# DC075B_POWER_SUPPLIES.net
KiCad netlist of a schematic drawn in Altium Designer
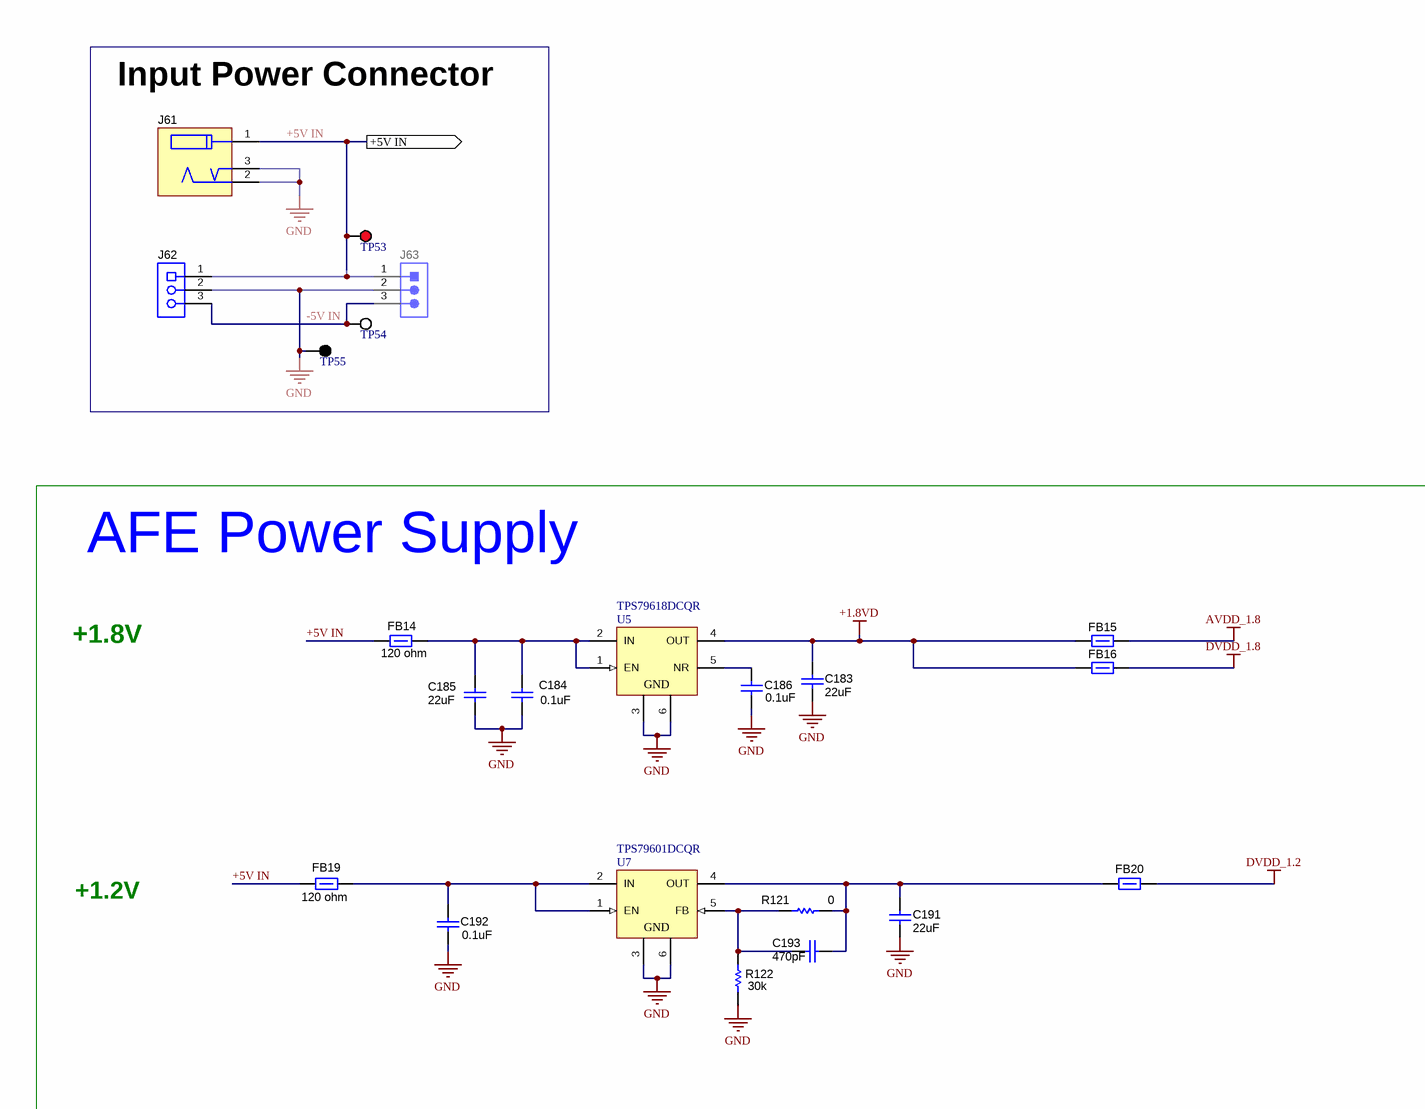
[diagram p0: DC075B_POWER_SUPPLIES.SchDoc, top left]
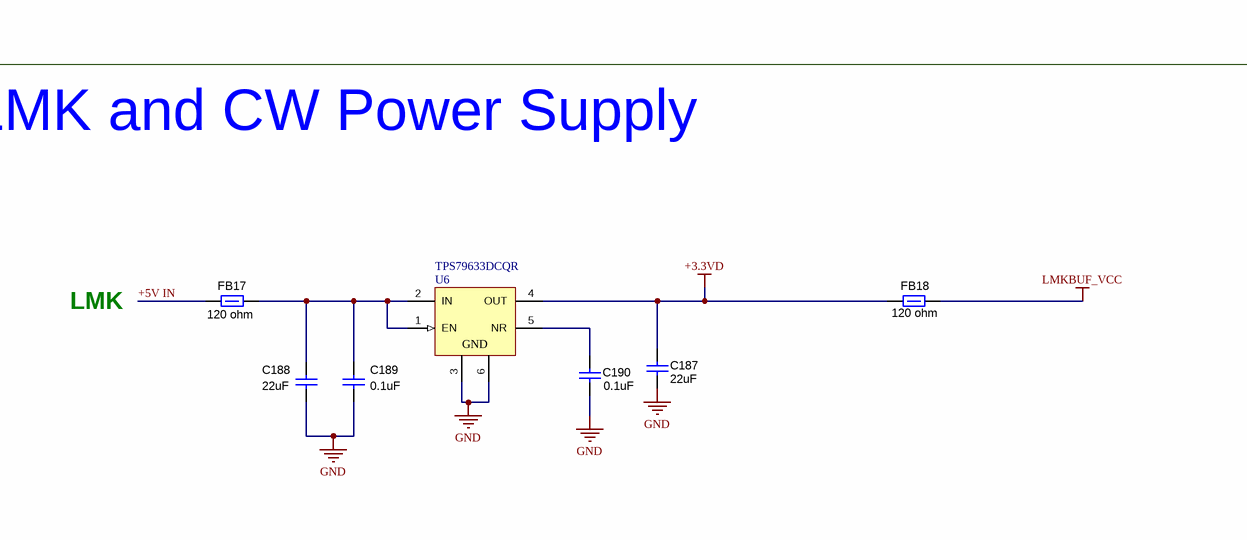
[diagram p1: DC075B_POWER_SUPPLIES.SchDoc, top right]
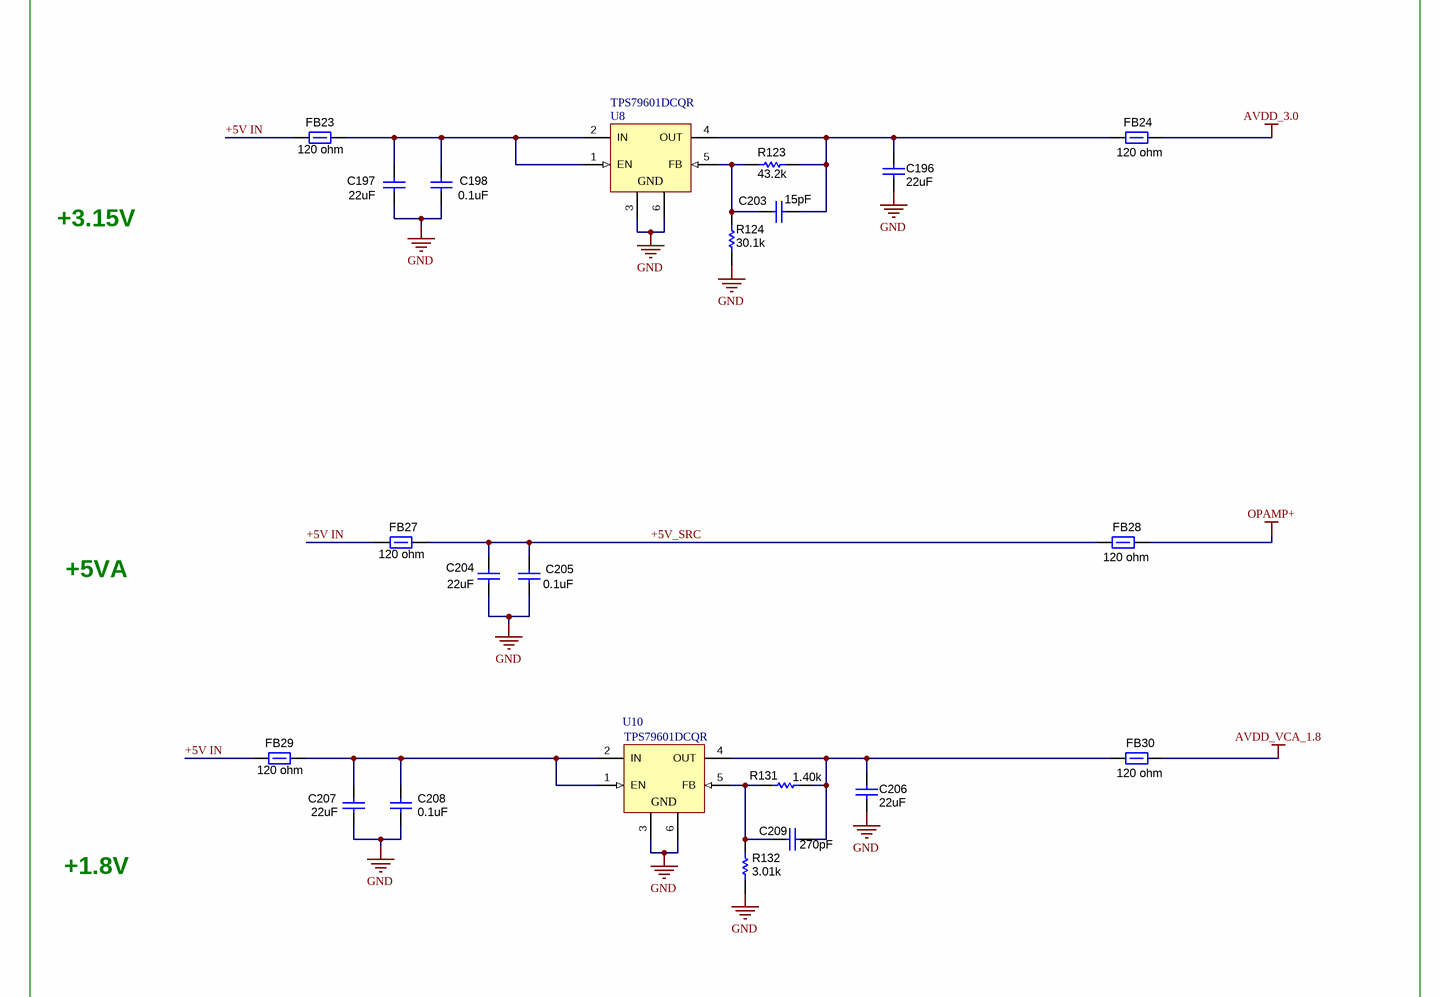
[diagram p2: DC075B_POWER_SUPPLIES.SchDoc, bottom left]
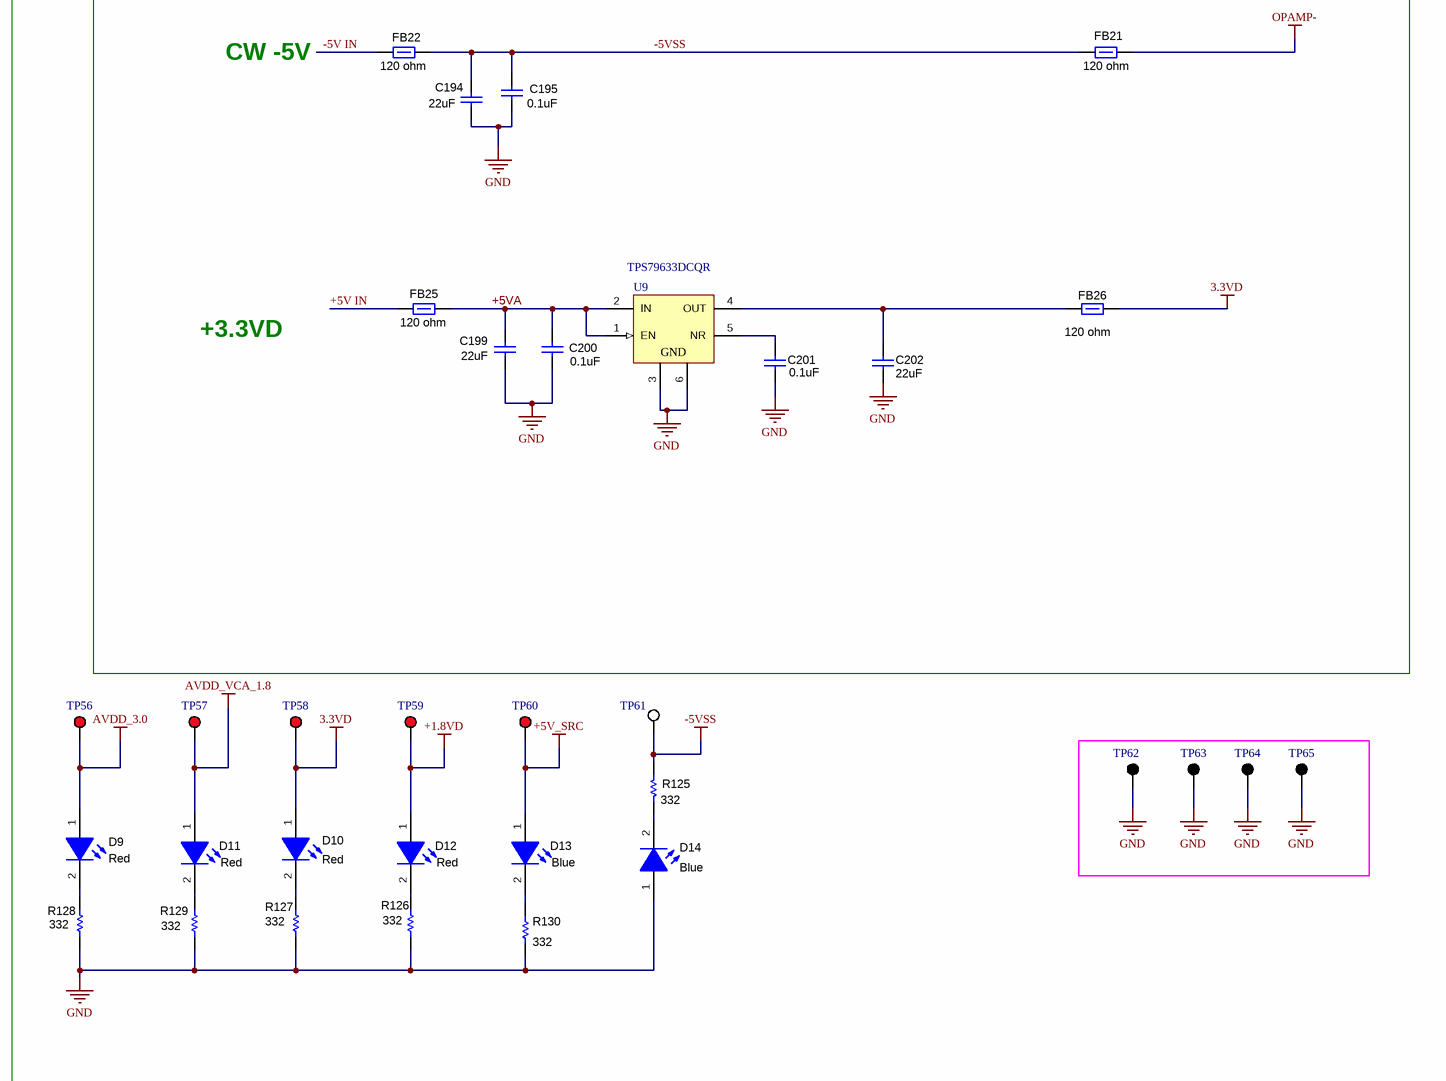
[diagram p3: DC075B_POWER_SUPPLIES.SchDoc, bottom right]

(export (version "E")
  (design (tool "Eeschema 10.0.6"))
  (components
    (comp (ref "C183")
      (value "GRM187R61A226ME15D")
      (footprint "0603")
      (description "CAP, CERM, 22 uF, 10 V, +/- 20%, X5R, 0603")
      (fields
        (field (name "VALUEDISPLAYED") "22uF")
        (field (name "MANUFACTURER") "MuRata")
        (field (name "PUBLISHER") "Texas Instruments")
      )
      (libsource (lib "Altium Vault - TI") (part "Capacitor"))
    )
    (comp (ref "C184")
      (value "0.1uF")
      (footprint "0603")
      (description "CAP, CERM, 0.1 µF, 25 V,+/- 10%, X5R, 0603")
      (fields
        (field (name "PARTNUMBER") "CL10A104KA8NNNC")
        (field (name "MANUFACTURER") "Samsung Electro-Mechanics")
      )
      (libsource (lib "Altium Vault - TI") (part "Capacitor"))
    )
    (comp (ref "C185")
      (value "1206YD226MAT2A")
      (footprint "1206_190")
      (description "CAP, CERM, 22 uF, 16 V, +/- 20%, X5R, 1206_190")
      (fields
        (field (name "VALUEDISPLAYED") "22uF")
        (field (name "MANUFACTURER") "AVX")
        (field (name "PUBLISHER") "Texas Instruments")
      )
      (libsource (lib "Altium Vault - TI") (part "Capacitor"))
    )
    (comp (ref "C186")
      (value "0.1uF")
      (footprint "0603")
      (description "CAP, CERM, 0.1 µF, 25 V,+/- 10%, X5R, 0603")
      (fields
        (field (name "PARTNUMBER") "CL10A104KA8NNNC")
        (field (name "MANUFACTURER") "Samsung Electro-Mechanics")
      )
      (libsource (lib "Altium Vault - TI") (part "Capacitor"))
    )
    (comp (ref "C187")
      (value "GRM187R61A226ME15D")
      (footprint "0603")
      (description "CAP, CERM, 22 uF, 10 V, +/- 20%, X5R, 0603")
      (fields
        (field (name "VALUEDISPLAYED") "22uF")
        (field (name "MANUFACTURER") "MuRata")
        (field (name "PUBLISHER") "Texas Instruments")
      )
      (libsource (lib "Altium Vault - TI") (part "Capacitor"))
    )
    (comp (ref "C188")
      (value "1206YD226MAT2A")
      (footprint "1206_190")
      (description "CAP, CERM, 22 uF, 16 V, +/- 20%, X5R, 1206_190")
      (fields
        (field (name "VALUEDISPLAYED") "22uF")
        (field (name "MANUFACTURER") "AVX")
        (field (name "PUBLISHER") "Texas Instruments")
      )
      (libsource (lib "Altium Vault - TI") (part "Capacitor"))
    )
    (comp (ref "C189")
      (value "0.1uF")
      (footprint "0603")
      (description "CAP, CERM, 0.1 µF, 25 V,+/- 10%, X5R, 0603")
      (fields
        (field (name "PARTNUMBER") "CL10A104KA8NNNC")
        (field (name "MANUFACTURER") "Samsung Electro-Mechanics")
      )
      (libsource (lib "Altium Vault - TI") (part "Capacitor"))
    )
    (comp (ref "C190")
      (value "0.1uF")
      (footprint "0603")
      (description "CAP, CERM, 0.1 µF, 25 V,+/- 10%, X5R, 0603")
      (fields
        (field (name "PARTNUMBER") "CL10A104KA8NNNC")
        (field (name "MANUFACTURER") "Samsung Electro-Mechanics")
      )
      (libsource (lib "Altium Vault - TI") (part "Capacitor"))
    )
    (comp (ref "C191")
      (value "GRM187R61A226ME15D")
      (footprint "0603")
      (description "CAP, CERM, 22 uF, 10 V, +/- 20%, X5R, 0603")
      (fields
        (field (name "VALUEDISPLAYED") "22uF")
        (field (name "MANUFACTURER") "MuRata")
        (field (name "PUBLISHER") "Texas Instruments")
      )
      (libsource (lib "Altium Vault - TI") (part "Capacitor"))
    )
    (comp (ref "C192")
      (value "0.1uF")
      (footprint "0603")
      (description "CAP, CERM, 0.1 µF, 25 V,+/- 10%, X5R, 0603")
      (fields
        (field (name "PARTNUMBER") "CL10A104KA8NNNC")
        (field (name "MANUFACTURER") "Samsung Electro-Mechanics")
      )
      (libsource (lib "Altium Vault - TI") (part "Capacitor"))
    )
    (comp (ref "C193")
      (value "470pF")
      (footprint "0603")
      (description "CAP, CERM, 470 pF, 50 V, +/- 5%, C0G/NP0, 0603")
      (fields
        (field (name "PARTNUMBER") "06035A471JAT2A")
        (field (name "MANUFACTURER") "AVX")
        (field (name "PUBLISHER") "Texas Instruments")
      )
      (libsource (lib "Altium Vault - TI") (part "Capacitor"))
    )
    (comp (ref "C194")
      (value "1206YD226MAT2A")
      (footprint "1206_190")
      (description "CAP, CERM, 22 uF, 16 V, +/- 20%, X5R, 1206_190")
      (fields
        (field (name "VALUEDISPLAYED") "22uF")
        (field (name "MANUFACTURER") "AVX")
        (field (name "PUBLISHER") "Texas Instruments")
      )
      (libsource (lib "Altium Vault - TI") (part "Capacitor"))
    )
    (comp (ref "C195")
      (value "0.1uF")
      (footprint "0603")
      (description "CAP, CERM, 0.1 µF, 25 V,+/- 10%, X5R, 0603")
      (fields
        (field (name "PARTNUMBER") "CL10A104KA8NNNC")
        (field (name "MANUFACTURER") "Samsung Electro-Mechanics")
      )
      (libsource (lib "Altium Vault - TI") (part "Capacitor"))
    )
    (comp (ref "C196")
      (value "GRM187R61A226ME15D")
      (footprint "0603")
      (description "CAP, CERM, 22 uF, 10 V, +/- 20%, X5R, 0603")
      (fields
        (field (name "VALUEDISPLAYED") "22uF")
        (field (name "MANUFACTURER") "MuRata")
        (field (name "PUBLISHER") "Texas Instruments")
      )
      (libsource (lib "Altium Vault - TI") (part "Capacitor"))
    )
    (comp (ref "C197")
      (value "1206YD226MAT2A")
      (footprint "1206_190")
      (description "CAP, CERM, 22 uF, 16 V, +/- 20%, X5R, 1206_190")
      (fields
        (field (name "VALUEDISPLAYED") "22uF")
        (field (name "MANUFACTURER") "AVX")
        (field (name "PUBLISHER") "Texas Instruments")
      )
      (libsource (lib "Altium Vault - TI") (part "Capacitor"))
    )
    (comp (ref "C198")
      (value "0.1uF")
      (footprint "0603")
      (description "CAP, CERM, 0.1 µF, 25 V,+/- 10%, X5R, 0603")
      (fields
        (field (name "PARTNUMBER") "CL10A104KA8NNNC")
        (field (name "MANUFACTURER") "Samsung Electro-Mechanics")
      )
      (libsource (lib "Altium Vault - TI") (part "Capacitor"))
    )
    (comp (ref "C199")
      (value "1206YD226MAT2A")
      (footprint "1206_190")
      (description "CAP, CERM, 22 uF, 16 V, +/- 20%, X5R, 1206_190")
      (fields
        (field (name "VALUEDISPLAYED") "22uF")
        (field (name "MANUFACTURER") "AVX")
        (field (name "PUBLISHER") "Texas Instruments")
      )
      (libsource (lib "Altium Vault - TI") (part "Capacitor"))
    )
    (comp (ref "C200")
      (value "0.1uF")
      (footprint "0603")
      (description "CAP, CERM, 0.1 µF, 25 V,+/- 10%, X5R, 0603")
      (fields
        (field (name "PARTNUMBER") "CL10A104KA8NNNC")
        (field (name "MANUFACTURER") "Samsung Electro-Mechanics")
      )
      (libsource (lib "Altium Vault - TI") (part "Capacitor"))
    )
    (comp (ref "C201")
      (value "0.1uF")
      (footprint "0603")
      (description "CAP, CERM, 0.1 µF, 25 V,+/- 10%, X5R, 0603")
      (fields
        (field (name "PARTNUMBER") "CL10A104KA8NNNC")
        (field (name "MANUFACTURER") "Samsung Electro-Mechanics")
      )
      (libsource (lib "Altium Vault - TI") (part "Capacitor"))
    )
    (comp (ref "C202")
      (value "GRM187R61A226ME15D")
      (footprint "0603")
      (description "CAP, CERM, 22 uF, 10 V, +/- 20%, X5R, 0603")
      (fields
        (field (name "VALUEDISPLAYED") "22uF")
        (field (name "MANUFACTURER") "MuRata")
        (field (name "PUBLISHER") "Texas Instruments")
      )
      (libsource (lib "Altium Vault - TI") (part "Capacitor"))
    )
    (comp (ref "C203")
      (value "06035A150JAT2A")
      (footprint "0603")
      (description "CAP, CERM, 15 pF, 50 V, +/- 5%, C0G/NP0, 0603")
      (fields
        (field (name "VALUEDISPLAYED") "15pF")
        (field (name "MANUFACTURER") "AVX")
        (field (name "PUBLISHER") "Texas Instruments")
      )
      (libsource (lib "Altium Vault - TI") (part "Capacitor"))
    )
    (comp (ref "C204")
      (value "1206YD226MAT2A")
      (footprint "1206_190")
      (description "CAP, CERM, 22 uF, 16 V, +/- 20%, X5R, 1206_190")
      (fields
        (field (name "VALUEDISPLAYED") "22uF")
        (field (name "MANUFACTURER") "AVX")
        (field (name "PUBLISHER") "Texas Instruments")
      )
      (libsource (lib "Altium Vault - TI") (part "Capacitor"))
    )
    (comp (ref "C205")
      (value "0.1uF")
      (footprint "0603")
      (description "CAP, CERM, 0.1 µF, 25 V,+/- 10%, X5R, 0603")
      (fields
        (field (name "PARTNUMBER") "CL10A104KA8NNNC")
        (field (name "MANUFACTURER") "Samsung Electro-Mechanics")
      )
      (libsource (lib "Altium Vault - TI") (part "Capacitor"))
    )
    (comp (ref "C206")
      (value "GRM187R61A226ME15D")
      (footprint "0603")
      (description "CAP, CERM, 22 uF, 10 V, +/- 20%, X5R, 0603")
      (fields
        (field (name "VALUEDISPLAYED") "22uF")
        (field (name "MANUFACTURER") "MuRata")
        (field (name "PUBLISHER") "Texas Instruments")
      )
      (libsource (lib "Altium Vault - TI") (part "Capacitor"))
    )
    (comp (ref "C207")
      (value "1206YD226MAT2A")
      (footprint "1206_190")
      (description "CAP, CERM, 22 uF, 16 V, +/- 20%, X5R, 1206_190")
      (fields
        (field (name "VALUEDISPLAYED") "22uF")
        (field (name "MANUFACTURER") "AVX")
        (field (name "PUBLISHER") "Texas Instruments")
      )
      (libsource (lib "Altium Vault - TI") (part "Capacitor"))
    )
    (comp (ref "C208")
      (value "0.1uF")
      (footprint "0603")
      (description "CAP, CERM, 0.1 µF, 25 V,+/- 10%, X5R, 0603")
      (fields
        (field (name "PARTNUMBER") "CL10A104KA8NNNC")
        (field (name "MANUFACTURER") "Samsung Electro-Mechanics")
      )
      (libsource (lib "Altium Vault - TI") (part "Capacitor"))
    )
    (comp (ref "C209")
      (value "C0603C271K5RACTU")
      (footprint "0603")
      (description "CAP, CERM, 270 pF, 50 V, +/- 10%, X7R, 0603")
      (fields
        (field (name "MANUFACTURER") "Kemet")
        (field (name "CAP_F") "270pF")
        (field (name "PUBLISHER") "Texas Instruments")
      )
      (libsource (lib "Altium Vault - TI") (part "Capacitor"))
    )
    (comp (ref "D9")
      (value "Red")
      (footprint "LED_LTST-C190_Red")
      (description "LED, Red, SMD")
      (fields (field (name "MANUFACTURER") "Lite-On") (field (name "PARTNUMBER") "LTST-C190CKT"))
      (libsource (lib "Altium Vault - TI") (part "CMP-0002842-2"))
    )
    (comp (ref "D10")
      (value "Red")
      (footprint "LED_LTST-C190_Red")
      (description "LED, Red, SMD")
      (fields (field (name "MANUFACTURER") "Lite-On") (field (name "PARTNUMBER") "LTST-C190CKT"))
      (libsource (lib "Altium Vault - TI") (part "CMP-0002842-2"))
    )
    (comp (ref "D11")
      (value "Red")
      (footprint "LED_LTST-C190_Red")
      (description "LED, Red, SMD")
      (fields (field (name "MANUFACTURER") "Lite-On") (field (name "PARTNUMBER") "LTST-C190CKT"))
      (libsource (lib "Altium Vault - TI") (part "CMP-0002842-2"))
    )
    (comp (ref "D12")
      (value "Red")
      (footprint "LED_LTST-C190_Red")
      (description "LED, Red, SMD")
      (fields (field (name "MANUFACTURER") "Lite-On") (field (name "PARTNUMBER") "LTST-C190CKT"))
      (libsource (lib "Altium Vault - TI") (part "CMP-0002842-2"))
    )
    (comp (ref "D13")
      (value "Blue")
      (footprint "LB Q39G_BLUE")
      (description "LED, Blue, SMD")
      (fields (field (name "MANUFACTURER") "OSRAM") (field (name "PARTNUMBER") "LB Q39G-L2N2-35-1"))
      (libsource (lib "Altium Vault - TI") (part "CMP-0002849-2"))
    )
    (comp (ref "D14")
      (value "Blue")
      (footprint "LB Q39G_BLUE")
      (description "LED, Blue, SMD")
      (fields (field (name "MANUFACTURER") "OSRAM") (field (name "PARTNUMBER") "LB Q39G-L2N2-35-1"))
      (libsource (lib "Altium Vault - TI") (part "CMP-0002849-2"))
    )
    (comp (ref "FB14")
      (value "120 ohm")
      (footprint "0805")
      (description "Ferrite Bead, 120 ohm @ 100 MHz, 0.8 A, 0805")
      (fields
        (field (name "MANUFACTURER") "MuRata")
        (field (name "PARTNUMBER") "BLM21AG121SN1D")
        (field (name "PUBLISHER") "Texas Instruments")
      )
      (libsource (lib "Altium Vault - TI") (part "Ferrite_Bead"))
    )
    (comp (ref "FB15")
      (value "BLM21AG121SN1D")
      (footprint "0805")
      (description "Ferrite Bead, 120 ohm @ 100 MHz, 0.8 A, 0805")
      (fields (field (name "MANUFACTURER") "MuRata") (field (name "PUBLISHER") "Texas Instruments"))
      (libsource (lib "Altium Vault - TI") (part "Ferrite_Bead"))
    )
    (comp (ref "FB16")
      (value "BLM21AG121SN1D")
      (footprint "0805")
      (description "Ferrite Bead, 120 ohm @ 100 MHz, 0.8 A, 0805")
      (fields (field (name "MANUFACTURER") "MuRata") (field (name "PUBLISHER") "Texas Instruments"))
      (libsource (lib "Altium Vault - TI") (part "Ferrite_Bead"))
    )
    (comp (ref "FB17")
      (value "120 ohm")
      (footprint "0805")
      (description "Ferrite Bead, 120 ohm @ 100 MHz, 0.8 A, 0805")
      (fields
        (field (name "MANUFACTURER") "MuRata")
        (field (name "PARTNUMBER") "BLM21AG121SN1D")
        (field (name "PUBLISHER") "Texas Instruments")
      )
      (libsource (lib "Altium Vault - TI") (part "Ferrite_Bead"))
    )
    (comp (ref "FB18")
      (value "120 ohm")
      (footprint "0805")
      (description "Ferrite Bead, 120 ohm @ 100 MHz, 0.8 A, 0805")
      (fields
        (field (name "MANUFACTURER") "MuRata")
        (field (name "PARTNUMBER") "BLM21AG121SN1D")
        (field (name "PUBLISHER") "Texas Instruments")
      )
      (libsource (lib "Altium Vault - TI") (part "Ferrite_Bead"))
    )
    (comp (ref "FB19")
      (value "120 ohm")
      (footprint "0805")
      (description "Ferrite Bead, 120 ohm @ 100 MHz, 0.8 A, 0805")
      (fields
        (field (name "MANUFACTURER") "MuRata")
        (field (name "PARTNUMBER") "BLM21AG121SN1D")
        (field (name "PUBLISHER") "Texas Instruments")
      )
      (libsource (lib "Altium Vault - TI") (part "Ferrite_Bead"))
    )
    (comp (ref "FB20")
      (value "BLM21AG121SN1D")
      (footprint "0805")
      (description "Ferrite Bead, 120 ohm @ 100 MHz, 0.8 A, 0805")
      (fields (field (name "MANUFACTURER") "MuRata") (field (name "PUBLISHER") "Texas Instruments"))
      (libsource (lib "Altium Vault - TI") (part "Ferrite_Bead"))
    )
    (comp (ref "FB21")
      (value "120 ohm")
      (footprint "0805")
      (description "Ferrite Bead, 120 ohm @ 100 MHz, 0.8 A, 0805")
      (fields
        (field (name "MANUFACTURER") "MuRata")
        (field (name "PARTNUMBER") "BLM21AG121SN1D")
        (field (name "PUBLISHER") "Texas Instruments")
      )
      (libsource (lib "Altium Vault - TI") (part "Ferrite_Bead"))
    )
    (comp (ref "FB22")
      (value "120 ohm")
      (footprint "0805")
      (description "Ferrite Bead, 120 ohm @ 100 MHz, 0.8 A, 0805")
      (fields
        (field (name "MANUFACTURER") "MuRata")
        (field (name "PARTNUMBER") "BLM21AG121SN1D")
        (field (name "PUBLISHER") "Texas Instruments")
      )
      (libsource (lib "Altium Vault - TI") (part "Ferrite_Bead"))
    )
    (comp (ref "FB23")
      (value "120 ohm")
      (footprint "0805")
      (description "Ferrite Bead, 120 ohm @ 100 MHz, 0.8 A, 0805")
      (fields
        (field (name "MANUFACTURER") "MuRata")
        (field (name "PARTNUMBER") "BLM21AG121SN1D")
        (field (name "PUBLISHER") "Texas Instruments")
      )
      (libsource (lib "Altium Vault - TI") (part "Ferrite_Bead"))
    )
    (comp (ref "FB24")
      (value "120 ohm")
      (footprint "0805")
      (description "Ferrite Bead, 120 ohm @ 100 MHz, 0.8 A, 0805")
      (fields
        (field (name "MANUFACTURER") "MuRata")
        (field (name "PARTNUMBER") "BLM21AG121SN1D")
        (field (name "PUBLISHER") "Texas Instruments")
      )
      (libsource (lib "Altium Vault - TI") (part "Ferrite_Bead"))
    )
    (comp (ref "FB25")
      (value "120 ohm")
      (footprint "0805")
      (description "Ferrite Bead, 120 ohm @ 100 MHz, 0.8 A, 0805")
      (fields
        (field (name "MANUFACTURER") "MuRata")
        (field (name "PARTNUMBER") "BLM21AG121SN1D")
        (field (name "PUBLISHER") "Texas Instruments")
      )
      (libsource (lib "Altium Vault - TI") (part "Ferrite_Bead"))
    )
    (comp (ref "FB26")
      (value "120 ohm")
      (footprint "0805")
      (description "Ferrite Bead, 120 ohm @ 100 MHz, 0.8 A, 0805")
      (fields
        (field (name "MANUFACTURER") "MuRata")
        (field (name "PARTNUMBER") "BLM21AG121SN1D")
        (field (name "PUBLISHER") "Texas Instruments")
      )
      (libsource (lib "Altium Vault - TI") (part "CMP-0003358-1"))
    )
    (comp (ref "FB27")
      (value "120 ohm")
      (footprint "0805")
      (description "Ferrite Bead, 120 ohm @ 100 MHz, 0.8 A, 0805")
      (fields
        (field (name "MANUFACTURER") "MuRata")
        (field (name "PARTNUMBER") "BLM21AG121SN1D")
        (field (name "PUBLISHER") "Texas Instruments")
      )
      (libsource (lib "Altium Vault - TI") (part "Ferrite_Bead"))
    )
    (comp (ref "FB28")
      (value "120 ohm")
      (footprint "0805")
      (description "Ferrite Bead, 120 ohm @ 100 MHz, 0.8 A, 0805")
      (fields
        (field (name "MANUFACTURER") "MuRata")
        (field (name "PARTNUMBER") "BLM21AG121SN1D")
        (field (name "PUBLISHER") "Texas Instruments")
      )
      (libsource (lib "Altium Vault - TI") (part "Ferrite_Bead"))
    )
    (comp (ref "FB29")
      (value "120 ohm")
      (footprint "0805")
      (description "Ferrite Bead, 120 ohm @ 100 MHz, 0.8 A, 0805")
      (fields
        (field (name "MANUFACTURER") "MuRata")
        (field (name "PARTNUMBER") "BLM21AG121SN1D")
        (field (name "PUBLISHER") "Texas Instruments")
      )
      (libsource (lib "Altium Vault - TI") (part "Ferrite_Bead"))
    )
    (comp (ref "FB30")
      (value "120 ohm")
      (footprint "0805")
      (description "Ferrite Bead, 120 ohm @ 100 MHz, 0.8 A, 0805")
      (fields
        (field (name "MANUFACTURER") "MuRata")
        (field (name "PARTNUMBER") "BLM21AG121SN1D")
        (field (name "PUBLISHER") "Texas Instruments")
      )
      (libsource (lib "Altium Vault - TI") (part "Ferrite_Bead"))
    )
    (comp (ref "J61")
      (value "RAPC722X")
      (footprint "CONN_RAPC722X")
      (description "Power Jack, mini, 2.1mm OD, R/A, TH")
      (fields (field (name "MANUFACTURER") "Switchcraft") (field (name "PUBLISHER") "Texas Instruments"))
      (libsource (lib "Altium Vault - TI") (part "CMP-0074940-1"))
    )
    (comp (ref "J62")
      (value "ED555/3DS")
      (footprint "TERM_BLK_ED555-3DS")
      (description "Terminal Block, 3.5mm Pitch, 3x1, TH")
      (fields
        (field (name "MANUFACTURER") "On-Shore Technology")
        (field (name "PUBLISHER") "Texas Instruments")
      )
      (libsource (lib "Altium Vault - TI") (part "CMP-0074916-1"))
    )
    (comp (ref "J63")
      (value "TSW-103-07-G-S")
      (footprint "TSW-103-07-G-S")
      (description "Header, 100mil, 3x1, Gold, TH")
      (fields (field (name "MANUFACTURER") "Samtec"))
      (libsource (lib "Altium Vault - TI") (part "CMP-0075407-2"))
    )
    (comp (ref "R121")
      (value "0")
      (footprint "0805_HV")
      (description "RES, 0, 5%, 0.125 W, AEC-Q200 Grade 0, 0805")
      (fields (field (name "PARTNUMBER") "CRCW08050000Z0EA") (field (name "MANUFACTURER") "Vishay-Dale"))
      (libsource (lib "Altium Vault - TI") (part "Resistor"))
    )
    (comp (ref "R122")
      (value "30k")
      (footprint "0805_HV")
      (description "RES, 30 k, 5%, 0.125 W, AEC-Q200 Grade 0, 0805")
      (fields (field (name "PARTNUMBER") "CRCW080530K0JNEA") (field (name "MANUFACTURER") "Vishay-Dale"))
      (libsource (lib "Altium Vault - TI") (part "Resistor"))
    )
    (comp (ref "R123")
      (value "RC0603FR-0743K2L")
      (footprint "0603")
      (description "RES, 43.2 k, 1%, 0.1 W, 0603")
      (fields (field (name "VALUEDISPLAYED") "43.2k") (field (name "MANUFACTURER") "Yageo"))
      (libsource (lib "Altium Vault - TI") (part "Resistor"))
    )
    (comp (ref "R124")
      (value "CRCW060330K1FKEA")
      (footprint "0603")
      (description "RES, 30.1 k, 1%, 0.1 W, AEC-Q200 Grade 0, 0603")
      (fields (field (name "VALUEDISPLAYED") "30.1k") (field (name "MANUFACTURER") "Vishay-Dale"))
      (libsource (lib "Altium Vault - TI") (part "Resistor"))
    )
    (comp (ref "R125")
      (value "332")
      (footprint "0402")
      (description "RES, 332, 1%, 0.063 W, AEC-Q200 Grade 0, 0402")
      (fields (field (name "MANUFACTURER") "Vishay-Dale") (field (name "PARTNUMBER") "CRCW0402332RFKED"))
      (libsource (lib "Altium Vault - TI") (part "Resistor"))
    )
    (comp (ref "R126")
      (value "332")
      (footprint "0402")
      (description "RES, 332, 1%, 0.063 W, AEC-Q200 Grade 0, 0402")
      (fields (field (name "MANUFACTURER") "Vishay-Dale") (field (name "PARTNUMBER") "CRCW0402332RFKED"))
      (libsource (lib "Altium Vault - TI") (part "Resistor"))
    )
    (comp (ref "R127")
      (value "332")
      (footprint "0402")
      (description "RES, 332, 1%, 0.063 W, AEC-Q200 Grade 0, 0402")
      (fields (field (name "MANUFACTURER") "Vishay-Dale") (field (name "PARTNUMBER") "CRCW0402332RFKED"))
      (libsource (lib "Altium Vault - TI") (part "Resistor"))
    )
    (comp (ref "R128")
      (value "332")
      (footprint "0402")
      (description "RES, 332, 1%, 0.063 W, AEC-Q200 Grade 0, 0402")
      (fields (field (name "MANUFACTURER") "Vishay-Dale") (field (name "PARTNUMBER") "CRCW0402332RFKED"))
      (libsource (lib "Altium Vault - TI") (part "Resistor"))
    )
    (comp (ref "R129")
      (value "332")
      (footprint "0402")
      (description "RES, 332, 1%, 0.063 W, AEC-Q200 Grade 0, 0402")
      (fields (field (name "MANUFACTURER") "Vishay-Dale") (field (name "PARTNUMBER") "CRCW0402332RFKED"))
      (libsource (lib "Altium Vault - TI") (part "Resistor"))
    )
    (comp (ref "R130")
      (value "332")
      (footprint "0402")
      (description "RES, 332, 1%, 0.063 W, AEC-Q200 Grade 0, 0402")
      (fields (field (name "MANUFACTURER") "Vishay-Dale") (field (name "PARTNUMBER") "CRCW0402332RFKED"))
      (libsource (lib "Altium Vault - TI") (part "Resistor"))
    )
    (comp (ref "R131")
      (value "CRCW06031K40FKEA")
      (footprint "0603")
      (description "RES, 1.40 k, 1%, 0.1 W, AEC-Q200 Grade 0, 0603")
      (fields (field (name "MANUFACTURER") "Vishay-Dale") (field (name "VALUEDISPLAYED") "1.40k"))
      (libsource (lib "Altium Vault - TI") (part "Resistor"))
    )
    (comp (ref "R132")
      (value "3.01k")
      (footprint "0603")
      (description "RES, 3.01 k, 1%, 0.1 W, AEC-Q200 Grade 0, 0603")
      (fields (field (name "PARTNUMBER") "CRCW06033K01FKEA") (field (name "MANUFACTURER") "Vishay-Dale"))
      (libsource (lib "Altium Vault - TI") (part "Resistor"))
    )
    (comp (ref "TP53")
      (value "5000")
      (footprint "Keystone5000")
      (description "Test Point, Miniature, Red, TH")
      (fields (field (name "MANUFACTURER") "Keystone") (field (name "PUBLISHER") "Texas Instruments"))
      (libsource (lib "Altium Vault - TI") (part "5000"))
    )
    (comp (ref "TP54")
      (value "5002")
      (footprint "Keystone5002")
      (description "Test Point, Miniature, White, TH")
      (fields (field (name "MANUFACTURER") "Keystone") (field (name "PUBLISHER") "Texas Instruments"))
      (libsource (lib "Altium Vault - TI") (part "5002"))
    )
    (comp (ref "TP55")
      (value "5001")
      (footprint "Keystone5001")
      (description "Test Point, Miniature, Black, TH")
      (fields (field (name "MANUFACTURER") "Keystone") (field (name "PUBLISHER") "Texas Instruments"))
      (libsource (lib "Altium Vault - TI") (part "5001"))
    )
    (comp (ref "TP56")
      (value "5000")
      (footprint "Keystone5000")
      (description "Test Point, Miniature, Red, TH")
      (fields (field (name "MANUFACTURER") "Keystone") (field (name "PUBLISHER") "Texas Instruments"))
      (libsource (lib "Altium Vault - TI") (part "5000"))
    )
    (comp (ref "TP57")
      (value "5000")
      (footprint "Keystone5000")
      (description "Test Point, Miniature, Red, TH")
      (fields (field (name "MANUFACTURER") "Keystone") (field (name "PUBLISHER") "Texas Instruments"))
      (libsource (lib "Altium Vault - TI") (part "5000"))
    )
    (comp (ref "TP58")
      (value "5000")
      (footprint "Keystone5000")
      (description "Test Point, Miniature, Red, TH")
      (fields (field (name "MANUFACTURER") "Keystone") (field (name "PUBLISHER") "Texas Instruments"))
      (libsource (lib "Altium Vault - TI") (part "5000"))
    )
    (comp (ref "TP59")
      (value "5000")
      (footprint "Keystone5000")
      (description "Test Point, Miniature, Red, TH")
      (fields (field (name "MANUFACTURER") "Keystone") (field (name "PUBLISHER") "Texas Instruments"))
      (libsource (lib "Altium Vault - TI") (part "5000"))
    )
    (comp (ref "TP60")
      (value "5000")
      (footprint "Keystone5000")
      (description "Test Point, Miniature, Red, TH")
      (fields (field (name "MANUFACTURER") "Keystone") (field (name "PUBLISHER") "Texas Instruments"))
      (libsource (lib "Altium Vault - TI") (part "5000"))
    )
    (comp (ref "TP61")
      (value "5002")
      (footprint "Keystone5002")
      (description "Test Point, Miniature, White, TH")
      (fields (field (name "MANUFACTURER") "Keystone") (field (name "PUBLISHER") "Texas Instruments"))
      (libsource (lib "Altium Vault - TI") (part "5002"))
    )
    (comp (ref "TP62")
      (value "5001")
      (footprint "Keystone5001")
      (description "Test Point, Miniature, Black, TH")
      (fields (field (name "MANUFACTURER") "Keystone") (field (name "PUBLISHER") "Texas Instruments"))
      (libsource (lib "Altium Vault - TI") (part "5001"))
    )
    (comp (ref "TP63")
      (value "5001")
      (footprint "Keystone5001")
      (description "Test Point, Miniature, Black, TH")
      (fields (field (name "MANUFACTURER") "Keystone") (field (name "PUBLISHER") "Texas Instruments"))
      (libsource (lib "Altium Vault - TI") (part "5001"))
    )
    (comp (ref "TP64")
      (value "5001")
      (footprint "Keystone5001")
      (description "Test Point, Miniature, Black, TH")
      (fields (field (name "MANUFACTURER") "Keystone") (field (name "PUBLISHER") "Texas Instruments"))
      (libsource (lib "Altium Vault - TI") (part "5001"))
    )
    (comp (ref "TP65")
      (value "5001")
      (footprint "Keystone5001")
      (description "Test Point, Miniature, Black, TH")
      (fields (field (name "MANUFACTURER") "Keystone") (field (name "PUBLISHER") "Texas Instruments"))
      (libsource (lib "Altium Vault - TI") (part "5001"))
    )
    (comp (ref "U5")
      (value "TPS79618DCQR")
      (footprint "DCQ0006A_N")
      (fields (field (name "MANUFACTURER") "Texas Instruments"))
      (libsource (lib "Altium Vault - TI") (part "TI-TPS7XXXXXXXX"))
    )
    (comp (ref "U6")
      (value "TPS79633DCQR")
      (footprint "DCQ0006A_N")
      (fields (field (name "MANUFACTURER") "Texas Instruments"))
      (libsource (lib "Altium Vault - TI") (part "TI-TPS7XXXXXXXX"))
    )
    (comp (ref "U7")
      (value "TPS79601DCQR")
      (footprint "DCQ0006A_N")
      (fields (field (name "MANUFACTURER") "Texas Instruments"))
      (libsource (lib "Altium Vault - TI") (part "TI-TPS7XX01-6"))
    )
    (comp (ref "U8")
      (value "TPS79601DCQR")
      (footprint "DCQ0006A_N")
      (fields (field (name "MANUFACTURER") "Texas Instruments"))
      (libsource (lib "Altium Vault - TI") (part "TI-TPS7XX01-6"))
    )
    (comp (ref "U9")
      (value "TPS79633DCQR")
      (footprint "DCQ0006A_N")
      (fields (field (name "MANUFACTURER") "Texas Instruments"))
      (libsource (lib "Altium Vault - TI") (part "TI-TPS7XXXXXXXX"))
    )
    (comp (ref "U10")
      (value "TPS79601DCQR")
      (footprint "DCQ0006A_N")
      (fields (field (name "MANUFACTURER") "Texas Instruments"))
      (libsource (lib "Altium Vault - TI") (part "TI-TPS7XX01-6"))
    )
  )
  (nets
    (net (code "1") (name "+1.8VD") (class "Default")
      (node (ref "C183") (pin "1") (pinfunction "1_1") (pintype "passive"))
      (node (ref "D12") (pin "1") (pinfunction "A_1") (pintype "passive"))
      (node (ref "FB15") (pin "1") (pinfunction "1_1") (pintype "passive"))
      (node (ref "FB16") (pin "1") (pinfunction "1_1") (pintype "passive"))
      (node (ref "TP59") (pin "1") (pintype "passive"))
      (node (ref "U5") (pin "4") (pinfunction "OUT_4") (pintype "power_in"))
    )
    (net (code "2") (name "+3.3VD") (class "Default")
      (node (ref "C187") (pin "1") (pinfunction "1_1") (pintype "passive"))
      (node (ref "FB18") (pin "1") (pinfunction "1_1") (pintype "passive"))
      (node (ref "U6") (pin "4") (pinfunction "OUT_4") (pintype "power_in"))
    )
    (net (code "3") (name "+5V_SRC") (class "Default")
      (node (ref "C204") (pin "2") (pinfunction "2_2") (pintype "passive"))
      (node (ref "C205") (pin "1") (pinfunction "1_1") (pintype "passive"))
      (node (ref "D13") (pin "1") (pinfunction "A_1") (pintype "passive"))
      (node (ref "FB27") (pin "2") (pinfunction "2_2") (pintype "passive"))
      (node (ref "FB28") (pin "1") (pinfunction "1_1") (pintype "passive"))
      (node (ref "TP60") (pin "1") (pintype "passive"))
    )
    (net (code "4") (name "-5VSS") (class "Default")
      (node (ref "C194") (pin "2") (pinfunction "2_2") (pintype "passive"))
      (node (ref "C195") (pin "1") (pinfunction "1_1") (pintype "passive"))
      (node (ref "FB21") (pin "1") (pinfunction "1_1") (pintype "passive"))
      (node (ref "FB22") (pin "2") (pinfunction "2_2") (pintype "passive"))
      (node (ref "R125") (pin "1") (pinfunction "1_1") (pintype "passive"))
      (node (ref "TP61") (pin "1") (pintype "passive"))
    )
    (net (code "5") (name "/+5V IN") (class "Default")
      (node (ref "FB14") (pin "1") (pinfunction "1_1") (pintype "passive"))
      (node (ref "FB17") (pin "1") (pinfunction "1_1") (pintype "passive"))
      (node (ref "FB19") (pin "1") (pinfunction "1_1") (pintype "passive"))
      (node (ref "FB23") (pin "1") (pinfunction "1_1") (pintype "passive"))
      (node (ref "FB25") (pin "1") (pinfunction "1_1") (pintype "passive"))
      (node (ref "FB27") (pin "1") (pinfunction "1_1") (pintype "passive"))
      (node (ref "FB29") (pin "1") (pinfunction "1_1") (pintype "passive"))
      (node (ref "J61") (pin "1") (pinfunction "1_1") (pintype "passive"))
      (node (ref "J62") (pin "1") (pinfunction "1_1") (pintype "passive"))
      (node (ref "J63") (pin "1") (pinfunction "1_1") (pintype "passive"))
      (node (ref "TP53") (pin "1") (pintype "passive"))
    )
    (net (code "6") (name "/+5VA") (class "Default")
      (node (ref "C199") (pin "2") (pinfunction "2_2") (pintype "passive"))
      (node (ref "C200") (pin "1") (pinfunction "1_1") (pintype "passive"))
      (node (ref "FB25") (pin "2") (pinfunction "2_2") (pintype "passive"))
      (node (ref "U9") (pin "1") (pinfunction "EN_1") (pintype "input"))
      (node (ref "U9") (pin "2") (pinfunction "IN_2") (pintype "power_in"))
    )
    (net (code "7") (name "/-5V IN") (class "Default")
      (node (ref "FB22") (pin "1") (pinfunction "1_1") (pintype "passive"))
      (node (ref "J62") (pin "3") (pinfunction "3_3") (pintype "passive"))
      (node (ref "J63") (pin "3") (pinfunction "3_3") (pintype "passive"))
      (node (ref "TP54") (pin "1") (pintype "passive"))
    )
    (net (code "8") (name "3.3VD") (class "Default")
      (node (ref "D10") (pin "1") (pinfunction "A_1") (pintype "passive"))
      (node (ref "FB26") (pin "2") (pinfunction "2_2") (pintype "passive"))
      (node (ref "TP58") (pin "1") (pintype "passive"))
    )
    (net (code "9") (name "AVDD_1.8") (class "Default")
      (node (ref "FB15") (pin "2") (pinfunction "2_2") (pintype "passive"))
    )
    (net (code "10") (name "AVDD_3.0") (class "Default")
      (node (ref "D9") (pin "1") (pinfunction "A_1") (pintype "passive"))
      (node (ref "FB24") (pin "2") (pinfunction "2_2") (pintype "passive"))
      (node (ref "TP56") (pin "1") (pintype "passive"))
    )
    (net (code "11") (name "AVDD_VCA_1.8") (class "Default")
      (node (ref "D11") (pin "1") (pinfunction "A_1") (pintype "passive"))
      (node (ref "FB30") (pin "2") (pinfunction "2_2") (pintype "passive"))
      (node (ref "TP57") (pin "1") (pintype "passive"))
    )
    (net (code "12") (name "DVDD_1.2") (class "Default")
      (node (ref "FB20") (pin "2") (pinfunction "2_2") (pintype "passive"))
    )
    (net (code "13") (name "DVDD_1.8") (class "Default")
      (node (ref "FB16") (pin "2") (pinfunction "2_2") (pintype "passive"))
    )
    (net (code "14") (name "GND") (class "Default")
      (node (ref "C183") (pin "2") (pinfunction "2_2") (pintype "passive"))
      (node (ref "C184") (pin "2") (pinfunction "2_2") (pintype "passive"))
      (node (ref "C185") (pin "1") (pinfunction "1_1") (pintype "passive"))
      (node (ref "C186") (pin "2") (pinfunction "2_2") (pintype "passive"))
      (node (ref "C187") (pin "2") (pinfunction "2_2") (pintype "passive"))
      (node (ref "C188") (pin "1") (pinfunction "1_1") (pintype "passive"))
      (node (ref "C189") (pin "2") (pinfunction "2_2") (pintype "passive"))
      (node (ref "C190") (pin "2") (pinfunction "2_2") (pintype "passive"))
      (node (ref "C191") (pin "2") (pinfunction "2_2") (pintype "passive"))
      (node (ref "C192") (pin "2") (pinfunction "2_2") (pintype "passive"))
      (node (ref "C194") (pin "1") (pinfunction "1_1") (pintype "passive"))
      (node (ref "C195") (pin "2") (pinfunction "2_2") (pintype "passive"))
      (node (ref "C196") (pin "2") (pinfunction "2_2") (pintype "passive"))
      (node (ref "C197") (pin "1") (pinfunction "1_1") (pintype "passive"))
      (node (ref "C198") (pin "2") (pinfunction "2_2") (pintype "passive"))
      (node (ref "C199") (pin "1") (pinfunction "1_1") (pintype "passive"))
      (node (ref "C200") (pin "2") (pinfunction "2_2") (pintype "passive"))
      (node (ref "C201") (pin "2") (pinfunction "2_2") (pintype "passive"))
      (node (ref "C202") (pin "2") (pinfunction "2_2") (pintype "passive"))
      (node (ref "C204") (pin "1") (pinfunction "1_1") (pintype "passive"))
      (node (ref "C205") (pin "2") (pinfunction "2_2") (pintype "passive"))
      (node (ref "C206") (pin "2") (pinfunction "2_2") (pintype "passive"))
      (node (ref "C207") (pin "1") (pinfunction "1_1") (pintype "passive"))
      (node (ref "C208") (pin "2") (pinfunction "2_2") (pintype "passive"))
      (node (ref "D14") (pin "1") (pinfunction "A_1") (pintype "passive"))
      (node (ref "J61") (pin "2") (pinfunction "2_2") (pintype "passive"))
      (node (ref "J61") (pin "3") (pinfunction "3_3") (pintype "passive"))
      (node (ref "J62") (pin "2") (pinfunction "2_2") (pintype "passive"))
      (node (ref "J63") (pin "2") (pinfunction "2_2") (pintype "passive"))
      (node (ref "R122") (pin "1") (pinfunction "1_1") (pintype "passive"))
      (node (ref "R124") (pin "2") (pinfunction "2_2") (pintype "passive"))
      (node (ref "R126") (pin "1") (pinfunction "1_1") (pintype "passive"))
      (node (ref "R127") (pin "1") (pinfunction "1_1") (pintype "passive"))
      (node (ref "R128") (pin "1") (pinfunction "1_1") (pintype "passive"))
      (node (ref "R129") (pin "1") (pinfunction "1_1") (pintype "passive"))
      (node (ref "R130") (pin "1") (pinfunction "1_1") (pintype "passive"))
      (node (ref "R132") (pin "1") (pinfunction "1_1") (pintype "passive"))
      (node (ref "TP55") (pin "1") (pintype "passive"))
      (node (ref "TP62") (pin "1") (pintype "passive"))
      (node (ref "TP63") (pin "1") (pintype "passive"))
      (node (ref "TP64") (pin "1") (pintype "passive"))
      (node (ref "TP65") (pin "1") (pintype "passive"))
      (node (ref "U10") (pin "3") (pinfunction "GND_3") (pintype "power_in"))
      (node (ref "U10") (pin "6") (pinfunction "GND_6") (pintype "power_in"))
      (node (ref "U5") (pin "3") (pinfunction "GND_3") (pintype "power_in"))
      (node (ref "U5") (pin "6") (pinfunction "GND_6") (pintype "power_in"))
      (node (ref "U6") (pin "3") (pinfunction "GND_3") (pintype "power_in"))
      (node (ref "U6") (pin "6") (pinfunction "GND_6") (pintype "power_in"))
      (node (ref "U7") (pin "3") (pinfunction "GND_3") (pintype "power_in"))
      (node (ref "U7") (pin "6") (pinfunction "GND_6") (pintype "power_in"))
      (node (ref "U8") (pin "3") (pinfunction "GND_3") (pintype "power_in"))
      (node (ref "U8") (pin "6") (pinfunction "GND_6") (pintype "power_in"))
      (node (ref "U9") (pin "3") (pinfunction "GND_3") (pintype "power_in"))
      (node (ref "U9") (pin "6") (pinfunction "GND_6") (pintype "power_in"))
    )
    (net (code "15") (name "LMKBUF_VCC") (class "Default")
      (node (ref "FB18") (pin "2") (pinfunction "2_2") (pintype "passive"))
    )
    (net (code "16") (name "Net-(D9-K)") (class "Default")
      (node (ref "D9") (pin "2") (pinfunction "K_2") (pintype "passive"))
      (node (ref "R128") (pin "2") (pinfunction "2_2") (pintype "passive"))
    )
    (net (code "17") (name "Net-(D10-K)") (class "Default")
      (node (ref "D10") (pin "2") (pinfunction "K_2") (pintype "passive"))
      (node (ref "R127") (pin "2") (pinfunction "2_2") (pintype "passive"))
    )
    (net (code "18") (name "Net-(D11-K)") (class "Default")
      (node (ref "D11") (pin "2") (pinfunction "K_2") (pintype "passive"))
      (node (ref "R129") (pin "2") (pinfunction "2_2") (pintype "passive"))
    )
    (net (code "19") (name "Net-(D12-K)") (class "Default")
      (node (ref "D12") (pin "2") (pinfunction "K_2") (pintype "passive"))
      (node (ref "R126") (pin "2") (pinfunction "2_2") (pintype "passive"))
    )
    (net (code "20") (name "Net-(D13-K)") (class "Default")
      (node (ref "D13") (pin "2") (pinfunction "K_2") (pintype "passive"))
      (node (ref "R130") (pin "2") (pinfunction "2_2") (pintype "passive"))
    )
    (net (code "21") (name "Net-(D14-K)") (class "Default")
      (node (ref "D14") (pin "2") (pinfunction "K_2") (pintype "passive"))
      (node (ref "R125") (pin "2") (pinfunction "2_2") (pintype "passive"))
    )
    (net (code "22") (name "Net-(U5-EN)") (class "Default")
      (node (ref "C184") (pin "1") (pinfunction "1_1") (pintype "passive"))
      (node (ref "C185") (pin "2") (pinfunction "2_2") (pintype "passive"))
      (node (ref "FB14") (pin "2") (pinfunction "2_2") (pintype "passive"))
      (node (ref "U5") (pin "1") (pinfunction "EN_1") (pintype "input"))
      (node (ref "U5") (pin "2") (pinfunction "IN_2") (pintype "power_in"))
    )
    (net (code "23") (name "Net-(U5-NR)") (class "Default")
      (node (ref "C186") (pin "1") (pinfunction "1_1") (pintype "passive"))
      (node (ref "U5") (pin "5") (pinfunction "NR_5") (pintype "passive"))
    )
    (net (code "24") (name "Net-(U6-EN)") (class "Default")
      (node (ref "C188") (pin "2") (pinfunction "2_2") (pintype "passive"))
      (node (ref "C189") (pin "1") (pinfunction "1_1") (pintype "passive"))
      (node (ref "FB17") (pin "2") (pinfunction "2_2") (pintype "passive"))
      (node (ref "U6") (pin "1") (pinfunction "EN_1") (pintype "input"))
      (node (ref "U6") (pin "2") (pinfunction "IN_2") (pintype "power_in"))
    )
    (net (code "25") (name "Net-(U6-NR)") (class "Default")
      (node (ref "C190") (pin "1") (pinfunction "1_1") (pintype "passive"))
      (node (ref "U6") (pin "5") (pinfunction "NR_5") (pintype "passive"))
    )
    (net (code "26") (name "Net-(U7-EN)") (class "Default")
      (node (ref "C192") (pin "1") (pinfunction "1_1") (pintype "passive"))
      (node (ref "FB19") (pin "2") (pinfunction "2_2") (pintype "passive"))
      (node (ref "U7") (pin "1") (pinfunction "EN_1") (pintype "input"))
      (node (ref "U7") (pin "2") (pinfunction "IN_2") (pintype "power_in"))
    )
    (net (code "27") (name "Net-(U7-FB)") (class "Default")
      (node (ref "C193") (pin "2") (pinfunction "2_2") (pintype "passive"))
      (node (ref "R121") (pin "1") (pinfunction "1_1") (pintype "passive"))
      (node (ref "R122") (pin "2") (pinfunction "2_2") (pintype "passive"))
      (node (ref "U7") (pin "5") (pinfunction "FB_5") (pintype "input"))
    )
    (net (code "28") (name "Net-(U7-OUT)") (class "Default")
      (node (ref "C191") (pin "1") (pinfunction "1_1") (pintype "passive"))
      (node (ref "C193") (pin "1") (pinfunction "1_1") (pintype "passive"))
      (node (ref "FB20") (pin "1") (pinfunction "1_1") (pintype "passive"))
      (node (ref "R121") (pin "2") (pinfunction "2_2") (pintype "passive"))
      (node (ref "U7") (pin "4") (pinfunction "OUT_4") (pintype "power_in"))
    )
    (net (code "29") (name "Net-(U8-EN)") (class "Default")
      (node (ref "C197") (pin "2") (pinfunction "2_2") (pintype "passive"))
      (node (ref "C198") (pin "1") (pinfunction "1_1") (pintype "passive"))
      (node (ref "FB23") (pin "2") (pinfunction "2_2") (pintype "passive"))
      (node (ref "U8") (pin "1") (pinfunction "EN_1") (pintype "input"))
      (node (ref "U8") (pin "2") (pinfunction "IN_2") (pintype "power_in"))
    )
    (net (code "30") (name "Net-(U8-FB)") (class "Default")
      (node (ref "C203") (pin "2") (pinfunction "2_2") (pintype "passive"))
      (node (ref "R123") (pin "1") (pinfunction "1_1") (pintype "passive"))
      (node (ref "R124") (pin "1") (pinfunction "1_1") (pintype "passive"))
      (node (ref "U8") (pin "5") (pinfunction "FB_5") (pintype "input"))
    )
    (net (code "31") (name "Net-(U8-OUT)") (class "Default")
      (node (ref "C196") (pin "1") (pinfunction "1_1") (pintype "passive"))
      (node (ref "C203") (pin "1") (pinfunction "1_1") (pintype "passive"))
      (node (ref "FB24") (pin "1") (pinfunction "1_1") (pintype "passive"))
      (node (ref "R123") (pin "2") (pinfunction "2_2") (pintype "passive"))
      (node (ref "U8") (pin "4") (pinfunction "OUT_4") (pintype "power_in"))
    )
    (net (code "32") (name "Net-(U9-NR)") (class "Default")
      (node (ref "C201") (pin "1") (pinfunction "1_1") (pintype "passive"))
      (node (ref "U9") (pin "5") (pinfunction "NR_5") (pintype "passive"))
    )
    (net (code "33") (name "Net-(U9-OUT)") (class "Default")
      (node (ref "C202") (pin "1") (pinfunction "1_1") (pintype "passive"))
      (node (ref "FB26") (pin "1") (pinfunction "1_1") (pintype "passive"))
      (node (ref "U9") (pin "4") (pinfunction "OUT_4") (pintype "power_in"))
    )
    (net (code "34") (name "Net-(U10-EN)") (class "Default")
      (node (ref "C207") (pin "2") (pinfunction "2_2") (pintype "passive"))
      (node (ref "C208") (pin "1") (pinfunction "1_1") (pintype "passive"))
      (node (ref "FB29") (pin "2") (pinfunction "2_2") (pintype "passive"))
      (node (ref "U10") (pin "1") (pinfunction "EN_1") (pintype "input"))
      (node (ref "U10") (pin "2") (pinfunction "IN_2") (pintype "power_in"))
    )
    (net (code "35") (name "Net-(U10-FB)") (class "Default")
      (node (ref "C209") (pin "2") (pinfunction "2_2") (pintype "passive"))
      (node (ref "R131") (pin "1") (pinfunction "1_1") (pintype "passive"))
      (node (ref "R132") (pin "2") (pinfunction "2_2") (pintype "passive"))
      (node (ref "U10") (pin "5") (pinfunction "FB_5") (pintype "input"))
    )
    (net (code "36") (name "Net-(U10-OUT)") (class "Default")
      (node (ref "C206") (pin "1") (pinfunction "1_1") (pintype "passive"))
      (node (ref "C209") (pin "1") (pinfunction "1_1") (pintype "passive"))
      (node (ref "FB30") (pin "1") (pinfunction "1_1") (pintype "passive"))
      (node (ref "R131") (pin "2") (pinfunction "2_2") (pintype "passive"))
      (node (ref "U10") (pin "4") (pinfunction "OUT_4") (pintype "power_in"))
    )
    (net (code "37") (name "OPAMP+") (class "Default")
      (node (ref "FB28") (pin "2") (pinfunction "2_2") (pintype "passive"))
    )
    (net (code "38") (name "OPAMP-") (class "Default")
      (node (ref "FB21") (pin "2") (pinfunction "2_2") (pintype "passive"))
    )
  )
)
